# source_selector.net
KiCad netlist of a schematic drawn in EAGLE
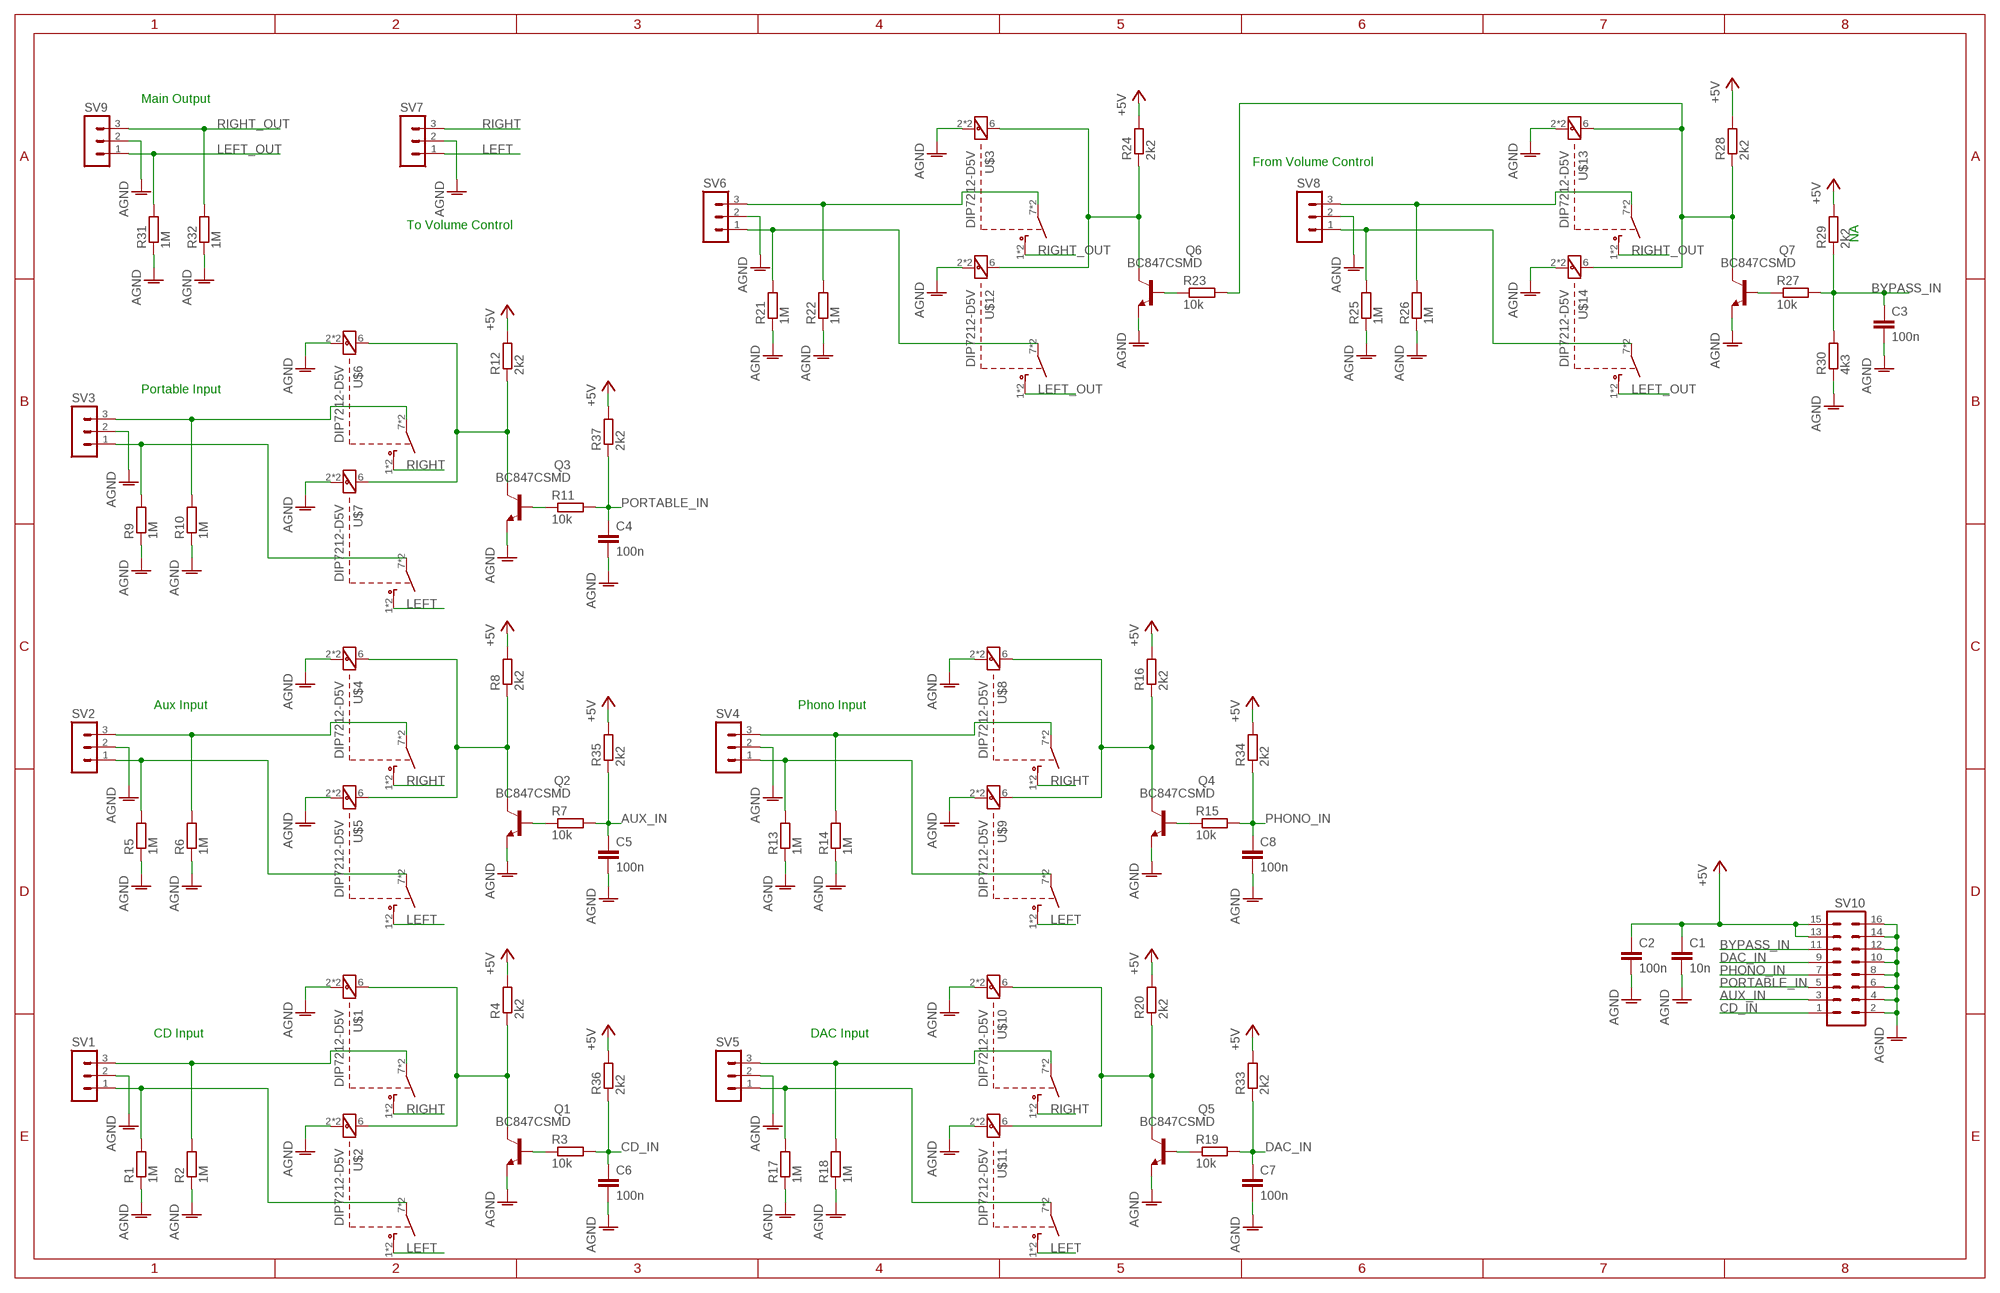
[diagram p0: schematic, sheet 1]

(export (version "E")
  (design (tool "Eeschema 10.0.6"))
  (components
    (comp (ref "C1")
      (value "10n")
      (footprint "eagle-import:C0603")
      (libsource (lib "eagle-import") (part "C-EUC0603"))
    )
    (comp (ref "C2")
      (value "100n")
      (footprint "eagle-import:C0603")
      (libsource (lib "eagle-import") (part "C-EUC0603"))
    )
    (comp (ref "C3")
      (value "100n")
      (footprint "eagle-import:C0603")
      (libsource (lib "eagle-import") (part "C-EUC0603"))
    )
    (comp (ref "C4")
      (value "100n")
      (footprint "eagle-import:C0603")
      (libsource (lib "eagle-import") (part "C-EUC0603"))
    )
    (comp (ref "C5")
      (value "100n")
      (footprint "eagle-import:C0603")
      (libsource (lib "eagle-import") (part "C-EUC0603"))
    )
    (comp (ref "C6")
      (value "100n")
      (footprint "eagle-import:C0603")
      (libsource (lib "eagle-import") (part "C-EUC0603"))
    )
    (comp (ref "C7")
      (value "100n")
      (footprint "eagle-import:C0603")
      (libsource (lib "eagle-import") (part "C-EUC0603"))
    )
    (comp (ref "C8")
      (value "100n")
      (footprint "eagle-import:C0603")
      (libsource (lib "eagle-import") (part "C-EUC0603"))
    )
    (comp (ref "Q1")
      (value "BC847CSMD")
      (footprint "eagle-import:SOT23")
      (libsource (lib "eagle-import") (part "BC847SMDC"))
    )
    (comp (ref "Q2")
      (value "BC847CSMD")
      (footprint "eagle-import:SOT23")
      (libsource (lib "eagle-import") (part "BC847SMDC"))
    )
    (comp (ref "Q3")
      (value "BC847CSMD")
      (footprint "eagle-import:SOT23")
      (libsource (lib "eagle-import") (part "BC847SMDC"))
    )
    (comp (ref "Q4")
      (value "BC847CSMD")
      (footprint "eagle-import:SOT23")
      (libsource (lib "eagle-import") (part "BC847SMDC"))
    )
    (comp (ref "Q5")
      (value "BC847CSMD")
      (footprint "eagle-import:SOT23")
      (libsource (lib "eagle-import") (part "BC847SMDC"))
    )
    (comp (ref "Q6")
      (value "BC847CSMD")
      (footprint "eagle-import:SOT23")
      (libsource (lib "eagle-import") (part "BC847SMDC"))
    )
    (comp (ref "Q7")
      (value "BC847CSMD")
      (footprint "eagle-import:SOT23")
      (libsource (lib "eagle-import") (part "BC847SMDC"))
    )
    (comp (ref "R1")
      (value "1M")
      (footprint "eagle-import:R0603")
      (libsource (lib "eagle-import") (part "R-EU_R0603"))
    )
    (comp (ref "R2")
      (value "1M")
      (footprint "eagle-import:R0603")
      (libsource (lib "eagle-import") (part "R-EU_R0603"))
    )
    (comp (ref "R3")
      (value "10k")
      (footprint "eagle-import:R0603")
      (libsource (lib "eagle-import") (part "R-EU_R0603"))
    )
    (comp (ref "R4")
      (value "2k2")
      (footprint "eagle-import:R0603")
      (libsource (lib "eagle-import") (part "R-EU_R0603"))
    )
    (comp (ref "R5")
      (value "1M")
      (footprint "eagle-import:R0603")
      (libsource (lib "eagle-import") (part "R-EU_R0603"))
    )
    (comp (ref "R6")
      (value "1M")
      (footprint "eagle-import:R0603")
      (libsource (lib "eagle-import") (part "R-EU_R0603"))
    )
    (comp (ref "R7")
      (value "10k")
      (footprint "eagle-import:R0603")
      (libsource (lib "eagle-import") (part "R-EU_R0603"))
    )
    (comp (ref "R8")
      (value "2k2")
      (footprint "eagle-import:R0603")
      (libsource (lib "eagle-import") (part "R-EU_R0603"))
    )
    (comp (ref "R9")
      (value "1M")
      (footprint "eagle-import:R0603")
      (libsource (lib "eagle-import") (part "R-EU_R0603"))
    )
    (comp (ref "R10")
      (value "1M")
      (footprint "eagle-import:R0603")
      (libsource (lib "eagle-import") (part "R-EU_R0603"))
    )
    (comp (ref "R11")
      (value "10k")
      (footprint "eagle-import:R0603")
      (libsource (lib "eagle-import") (part "R-EU_R0603"))
    )
    (comp (ref "R12")
      (value "2k2")
      (footprint "eagle-import:R0603")
      (libsource (lib "eagle-import") (part "R-EU_R0603"))
    )
    (comp (ref "R13")
      (value "1M")
      (footprint "eagle-import:R0603")
      (libsource (lib "eagle-import") (part "R-EU_R0603"))
    )
    (comp (ref "R14")
      (value "1M")
      (footprint "eagle-import:R0603")
      (libsource (lib "eagle-import") (part "R-EU_R0603"))
    )
    (comp (ref "R15")
      (value "10k")
      (footprint "eagle-import:R0603")
      (libsource (lib "eagle-import") (part "R-EU_R0603"))
    )
    (comp (ref "R16")
      (value "2k2")
      (footprint "eagle-import:R0603")
      (libsource (lib "eagle-import") (part "R-EU_R0603"))
    )
    (comp (ref "R17")
      (value "1M")
      (footprint "eagle-import:R0603")
      (libsource (lib "eagle-import") (part "R-EU_R0603"))
    )
    (comp (ref "R18")
      (value "1M")
      (footprint "eagle-import:R0603")
      (libsource (lib "eagle-import") (part "R-EU_R0603"))
    )
    (comp (ref "R19")
      (value "10k")
      (footprint "eagle-import:R0603")
      (libsource (lib "eagle-import") (part "R-EU_R0603"))
    )
    (comp (ref "R20")
      (value "2k2")
      (footprint "eagle-import:R0603")
      (libsource (lib "eagle-import") (part "R-EU_R0603"))
    )
    (comp (ref "R21")
      (value "1M")
      (footprint "eagle-import:R0603")
      (libsource (lib "eagle-import") (part "R-EU_R0603"))
    )
    (comp (ref "R22")
      (value "1M")
      (footprint "eagle-import:R0603")
      (libsource (lib "eagle-import") (part "R-EU_R0603"))
    )
    (comp (ref "R23")
      (value "10k")
      (footprint "eagle-import:R0603")
      (libsource (lib "eagle-import") (part "R-EU_R0603"))
    )
    (comp (ref "R24")
      (value "2k2")
      (footprint "eagle-import:R0603")
      (libsource (lib "eagle-import") (part "R-EU_R0603"))
    )
    (comp (ref "R25")
      (value "1M")
      (footprint "eagle-import:R0603")
      (libsource (lib "eagle-import") (part "R-EU_R0603"))
    )
    (comp (ref "R26")
      (value "1M")
      (footprint "eagle-import:R0603")
      (libsource (lib "eagle-import") (part "R-EU_R0603"))
    )
    (comp (ref "R27")
      (value "10k")
      (footprint "eagle-import:R0603")
      (libsource (lib "eagle-import") (part "R-EU_R0603"))
    )
    (comp (ref "R28")
      (value "2k2")
      (footprint "eagle-import:R0603")
      (libsource (lib "eagle-import") (part "R-EU_R0603"))
    )
    (comp (ref "R29")
      (value "2k2")
      (footprint "eagle-import:R0603")
      (libsource (lib "eagle-import") (part "R-EU_R0603"))
    )
    (comp (ref "R30")
      (value "4k3")
      (footprint "eagle-import:R0603")
      (libsource (lib "eagle-import") (part "R-EU_R0603"))
    )
    (comp (ref "R31")
      (value "1M")
      (footprint "eagle-import:R0603")
      (libsource (lib "eagle-import") (part "R-EU_R0603"))
    )
    (comp (ref "R32")
      (value "1M")
      (footprint "eagle-import:R0603")
      (libsource (lib "eagle-import") (part "R-EU_R0603"))
    )
    (comp (ref "R33")
      (value "2k2")
      (footprint "eagle-import:R0603")
      (libsource (lib "eagle-import") (part "R-EU_R0603"))
    )
    (comp (ref "R34")
      (value "2k2")
      (footprint "eagle-import:R0603")
      (libsource (lib "eagle-import") (part "R-EU_R0603"))
    )
    (comp (ref "R35")
      (value "2k2")
      (footprint "eagle-import:R0603")
      (libsource (lib "eagle-import") (part "R-EU_R0603"))
    )
    (comp (ref "R36")
      (value "2k2")
      (footprint "eagle-import:R0603")
      (libsource (lib "eagle-import") (part "R-EU_R0603"))
    )
    (comp (ref "R37")
      (value "2k2")
      (footprint "eagle-import:R0603")
      (libsource (lib "eagle-import") (part "R-EU_R0603"))
    )
    (comp (ref "SV1")
      (value "MA03-1")
      (footprint "eagle-import:MA03-1")
      (libsource (lib "eagle-import") (part "MA03-1"))
    )
    (comp (ref "SV2")
      (value "MA03-1")
      (footprint "eagle-import:MA03-1")
      (libsource (lib "eagle-import") (part "MA03-1"))
    )
    (comp (ref "SV3")
      (value "MA03-1")
      (footprint "eagle-import:MA03-1")
      (libsource (lib "eagle-import") (part "MA03-1"))
    )
    (comp (ref "SV4")
      (value "MA03-1")
      (footprint "eagle-import:MA03-1")
      (libsource (lib "eagle-import") (part "MA03-1"))
    )
    (comp (ref "SV5")
      (value "MA03-1")
      (footprint "eagle-import:MA03-1")
      (libsource (lib "eagle-import") (part "MA03-1"))
    )
    (comp (ref "SV6")
      (value "MA03-1")
      (footprint "eagle-import:MA03-1")
      (libsource (lib "eagle-import") (part "MA03-1"))
    )
    (comp (ref "SV7")
      (value "MA03-1")
      (footprint "eagle-import:MA03-1")
      (libsource (lib "eagle-import") (part "MA03-1"))
    )
    (comp (ref "SV8")
      (value "MA03-1")
      (footprint "eagle-import:MA03-1")
      (libsource (lib "eagle-import") (part "MA03-1"))
    )
    (comp (ref "SV9")
      (value "MA03-1")
      (footprint "eagle-import:MA03-1")
      (libsource (lib "eagle-import") (part "MA03-1"))
    )
    (comp (ref "SV10")
      (value "MA08-2")
      (footprint "eagle-import:MA08-2")
      (libsource (lib "eagle-import") (part "MA08-2"))
    )
    (comp (ref "U$1")
      (value "DIP7212-D5V")
      (footprint "eagle-import:DP-07")
      (libsource (lib "eagle-import") (part "DIP7212-D5V"))
    )
    (comp (ref "U$2")
      (value "DIP7212-D5V")
      (footprint "eagle-import:DP-07")
      (libsource (lib "eagle-import") (part "DIP7212-D5V"))
    )
    (comp (ref "U$3")
      (value "DIP7212-D5V")
      (footprint "eagle-import:DP-07")
      (libsource (lib "eagle-import") (part "DIP7212-D5V"))
    )
    (comp (ref "U$4")
      (value "DIP7212-D5V")
      (footprint "eagle-import:DP-07")
      (libsource (lib "eagle-import") (part "DIP7212-D5V"))
    )
    (comp (ref "U$5")
      (value "DIP7212-D5V")
      (footprint "eagle-import:DP-07")
      (libsource (lib "eagle-import") (part "DIP7212-D5V"))
    )
    (comp (ref "U$6")
      (value "DIP7212-D5V")
      (footprint "eagle-import:DP-07")
      (libsource (lib "eagle-import") (part "DIP7212-D5V"))
    )
    (comp (ref "U$7")
      (value "DIP7212-D5V")
      (footprint "eagle-import:DP-07")
      (libsource (lib "eagle-import") (part "DIP7212-D5V"))
    )
    (comp (ref "U$8")
      (value "DIP7212-D5V")
      (footprint "eagle-import:DP-07")
      (libsource (lib "eagle-import") (part "DIP7212-D5V"))
    )
    (comp (ref "U$9")
      (value "DIP7212-D5V")
      (footprint "eagle-import:DP-07")
      (libsource (lib "eagle-import") (part "DIP7212-D5V"))
    )
    (comp (ref "U$10")
      (value "DIP7212-D5V")
      (footprint "eagle-import:DP-07")
      (libsource (lib "eagle-import") (part "DIP7212-D5V"))
    )
    (comp (ref "U$11")
      (value "DIP7212-D5V")
      (footprint "eagle-import:DP-07")
      (libsource (lib "eagle-import") (part "DIP7212-D5V"))
    )
    (comp (ref "U$12")
      (value "DIP7212-D5V")
      (footprint "eagle-import:DP-07")
      (libsource (lib "eagle-import") (part "DIP7212-D5V"))
    )
    (comp (ref "U$13")
      (value "DIP7212-D5V")
      (footprint "eagle-import:DP-07")
      (libsource (lib "eagle-import") (part "DIP7212-D5V"))
    )
    (comp (ref "U$14")
      (value "DIP7212-D5V")
      (footprint "eagle-import:DP-07")
      (libsource (lib "eagle-import") (part "DIP7212-D5V"))
    )
  )
  (nets
    (net (code "1") (name "+5V") (class "Default")
      (node (ref "C1") (pin "1") (pinfunction "1_1") (pintype "passive"))
      (node (ref "C2") (pin "1") (pinfunction "1_1") (pintype "passive"))
      (node (ref "R12") (pin "2") (pinfunction "2_2") (pintype "passive"))
      (node (ref "R16") (pin "2") (pinfunction "2_2") (pintype "passive"))
      (node (ref "R20") (pin "2") (pinfunction "2_2") (pintype "passive"))
      (node (ref "R24") (pin "2") (pinfunction "2_2") (pintype "passive"))
      (node (ref "R28") (pin "2") (pinfunction "2_2") (pintype "passive"))
      (node (ref "R29") (pin "2") (pinfunction "2_2") (pintype "passive"))
      (node (ref "R33") (pin "2") (pinfunction "2_2") (pintype "passive"))
      (node (ref "R34") (pin "2") (pinfunction "2_2") (pintype "passive"))
      (node (ref "R35") (pin "2") (pinfunction "2_2") (pintype "passive"))
      (node (ref "R36") (pin "2") (pinfunction "2_2") (pintype "passive"))
      (node (ref "R37") (pin "2") (pinfunction "2_2") (pintype "passive"))
      (node (ref "R4") (pin "2") (pinfunction "2_2") (pintype "passive"))
      (node (ref "R8") (pin "2") (pinfunction "2_2") (pintype "passive"))
      (node (ref "SV10") (pin "13") (pinfunction "13_13") (pintype "passive"))
      (node (ref "SV10") (pin "15") (pinfunction "15_15") (pintype "passive"))
    )
    (net (code "2") (name "/AUX_IN") (class "Default")
      (node (ref "C5") (pin "1") (pinfunction "1_1") (pintype "passive"))
      (node (ref "R35") (pin "1") (pinfunction "1_1") (pintype "passive"))
      (node (ref "R7") (pin "2") (pinfunction "2_2") (pintype "passive"))
      (node (ref "SV10") (pin "3") (pinfunction "3_3") (pintype "passive"))
    )
    (net (code "3") (name "/BYPASS_IN") (class "Default")
      (node (ref "C3") (pin "1") (pinfunction "1_1") (pintype "passive"))
      (node (ref "R27") (pin "2") (pinfunction "2_2") (pintype "passive"))
      (node (ref "R29") (pin "1") (pinfunction "1_1") (pintype "passive"))
      (node (ref "R30") (pin "2") (pinfunction "2_2") (pintype "passive"))
      (node (ref "SV10") (pin "11") (pinfunction "11_11") (pintype "passive"))
    )
    (net (code "4") (name "/CD_IN") (class "Default")
      (node (ref "C6") (pin "1") (pinfunction "1_1") (pintype "passive"))
      (node (ref "R3") (pin "2") (pinfunction "2_2") (pintype "passive"))
      (node (ref "R36") (pin "1") (pinfunction "1_1") (pintype "passive"))
      (node (ref "SV10") (pin "1") (pinfunction "1_1") (pintype "passive"))
    )
    (net (code "5") (name "/DAC_IN") (class "Default")
      (node (ref "C7") (pin "1") (pinfunction "1_1") (pintype "passive"))
      (node (ref "R19") (pin "2") (pinfunction "2_2") (pintype "passive"))
      (node (ref "R33") (pin "1") (pinfunction "1_1") (pintype "passive"))
      (node (ref "SV10") (pin "9") (pinfunction "9_9") (pintype "passive"))
    )
    (net (code "6") (name "/LEFT") (class "Default")
      (node (ref "SV7") (pin "1") (pinfunction "1_1") (pintype "passive"))
      (node (ref "U$11") (pin "1") (pinfunction "6_1") (pintype "passive"))
      (node (ref "U$11") (pin "14") (pinfunction "6_14") (pintype "passive"))
      (node (ref "U$2") (pin "1") (pinfunction "6_1") (pintype "passive"))
      (node (ref "U$2") (pin "14") (pinfunction "6_14") (pintype "passive"))
      (node (ref "U$5") (pin "1") (pinfunction "6_1") (pintype "passive"))
      (node (ref "U$5") (pin "14") (pinfunction "6_14") (pintype "passive"))
      (node (ref "U$7") (pin "1") (pinfunction "6_1") (pintype "passive"))
      (node (ref "U$7") (pin "14") (pinfunction "6_14") (pintype "passive"))
      (node (ref "U$9") (pin "1") (pinfunction "6_1") (pintype "passive"))
      (node (ref "U$9") (pin "14") (pinfunction "6_14") (pintype "passive"))
    )
    (net (code "7") (name "/LEFT_OUT") (class "Default")
      (node (ref "R31") (pin "2") (pinfunction "2_2") (pintype "passive"))
      (node (ref "SV9") (pin "1") (pinfunction "1_1") (pintype "passive"))
      (node (ref "U$12") (pin "1") (pinfunction "6_1") (pintype "passive"))
      (node (ref "U$12") (pin "14") (pinfunction "6_14") (pintype "passive"))
      (node (ref "U$14") (pin "1") (pinfunction "6_1") (pintype "passive"))
      (node (ref "U$14") (pin "14") (pinfunction "6_14") (pintype "passive"))
    )
    (net (code "8") (name "/PHONO_IN") (class "Default")
      (node (ref "C8") (pin "1") (pinfunction "1_1") (pintype "passive"))
      (node (ref "R15") (pin "2") (pinfunction "2_2") (pintype "passive"))
      (node (ref "R34") (pin "1") (pinfunction "1_1") (pintype "passive"))
      (node (ref "SV10") (pin "7") (pinfunction "7_7") (pintype "passive"))
    )
    (net (code "9") (name "/PORTABLE_IN") (class "Default")
      (node (ref "C4") (pin "1") (pinfunction "1_1") (pintype "passive"))
      (node (ref "R11") (pin "2") (pinfunction "2_2") (pintype "passive"))
      (node (ref "R37") (pin "1") (pinfunction "1_1") (pintype "passive"))
      (node (ref "SV10") (pin "5") (pinfunction "5_5") (pintype "passive"))
    )
    (net (code "10") (name "/RIGHT") (class "Default")
      (node (ref "SV7") (pin "3") (pinfunction "3_3") (pintype "passive"))
      (node (ref "U$1") (pin "1") (pinfunction "6_1") (pintype "passive"))
      (node (ref "U$1") (pin "14") (pinfunction "6_14") (pintype "passive"))
      (node (ref "U$10") (pin "1") (pinfunction "6_1") (pintype "passive"))
      (node (ref "U$10") (pin "14") (pinfunction "6_14") (pintype "passive"))
      (node (ref "U$4") (pin "1") (pinfunction "6_1") (pintype "passive"))
      (node (ref "U$4") (pin "14") (pinfunction "6_14") (pintype "passive"))
      (node (ref "U$6") (pin "1") (pinfunction "6_1") (pintype "passive"))
      (node (ref "U$6") (pin "14") (pinfunction "6_14") (pintype "passive"))
      (node (ref "U$8") (pin "1") (pinfunction "6_1") (pintype "passive"))
      (node (ref "U$8") (pin "14") (pinfunction "6_14") (pintype "passive"))
    )
    (net (code "11") (name "/RIGHT_OUT") (class "Default")
      (node (ref "R32") (pin "2") (pinfunction "2_2") (pintype "passive"))
      (node (ref "SV9") (pin "3") (pinfunction "3_3") (pintype "passive"))
      (node (ref "U$13") (pin "1") (pinfunction "6_1") (pintype "passive"))
      (node (ref "U$13") (pin "14") (pinfunction "6_14") (pintype "passive"))
      (node (ref "U$3") (pin "1") (pinfunction "6_1") (pintype "passive"))
      (node (ref "U$3") (pin "14") (pinfunction "6_14") (pintype "passive"))
    )
    (net (code "12") (name "AGND") (class "Default")
      (node (ref "C1") (pin "2") (pinfunction "2_2") (pintype "passive"))
      (node (ref "C2") (pin "2") (pinfunction "2_2") (pintype "passive"))
      (node (ref "C3") (pin "2") (pinfunction "2_2") (pintype "passive"))
      (node (ref "C4") (pin "2") (pinfunction "2_2") (pintype "passive"))
      (node (ref "C5") (pin "2") (pinfunction "2_2") (pintype "passive"))
      (node (ref "C6") (pin "2") (pinfunction "2_2") (pintype "passive"))
      (node (ref "C7") (pin "2") (pinfunction "2_2") (pintype "passive"))
      (node (ref "C8") (pin "2") (pinfunction "2_2") (pintype "passive"))
      (node (ref "Q1") (pin "2") (pinfunction "E_2") (pintype "passive"))
      (node (ref "Q2") (pin "2") (pinfunction "E_2") (pintype "passive"))
      (node (ref "Q3") (pin "2") (pinfunction "E_2") (pintype "passive"))
      (node (ref "Q4") (pin "2") (pinfunction "E_2") (pintype "passive"))
      (node (ref "Q5") (pin "2") (pinfunction "E_2") (pintype "passive"))
      (node (ref "Q6") (pin "2") (pinfunction "E_2") (pintype "passive"))
      (node (ref "Q7") (pin "2") (pinfunction "E_2") (pintype "passive"))
      (node (ref "R1") (pin "1") (pinfunction "1_1") (pintype "passive"))
      (node (ref "R10") (pin "1") (pinfunction "1_1") (pintype "passive"))
      (node (ref "R13") (pin "1") (pinfunction "1_1") (pintype "passive"))
      (node (ref "R14") (pin "1") (pinfunction "1_1") (pintype "passive"))
      (node (ref "R17") (pin "1") (pinfunction "1_1") (pintype "passive"))
      (node (ref "R18") (pin "1") (pinfunction "1_1") (pintype "passive"))
      (node (ref "R2") (pin "1") (pinfunction "1_1") (pintype "passive"))
      (node (ref "R21") (pin "1") (pinfunction "1_1") (pintype "passive"))
      (node (ref "R22") (pin "1") (pinfunction "1_1") (pintype "passive"))
      (node (ref "R25") (pin "1") (pinfunction "1_1") (pintype "passive"))
      (node (ref "R26") (pin "1") (pinfunction "1_1") (pintype "passive"))
      (node (ref "R30") (pin "1") (pinfunction "1_1") (pintype "passive"))
      (node (ref "R31") (pin "1") (pinfunction "1_1") (pintype "passive"))
      (node (ref "R32") (pin "1") (pinfunction "1_1") (pintype "passive"))
      (node (ref "R5") (pin "1") (pinfunction "1_1") (pintype "passive"))
      (node (ref "R6") (pin "1") (pinfunction "1_1") (pintype "passive"))
      (node (ref "R9") (pin "1") (pinfunction "1_1") (pintype "passive"))
      (node (ref "SV1") (pin "2") (pinfunction "2_2") (pintype "passive"))
      (node (ref "SV10") (pin "10") (pinfunction "10_10") (pintype "passive"))
      (node (ref "SV10") (pin "12") (pinfunction "12_12") (pintype "passive"))
      (node (ref "SV10") (pin "14") (pinfunction "14_14") (pintype "passive"))
      (node (ref "SV10") (pin "16") (pinfunction "16_16") (pintype "passive"))
      (node (ref "SV10") (pin "2") (pinfunction "2_2") (pintype "passive"))
      (node (ref "SV10") (pin "4") (pinfunction "4_4") (pintype "passive"))
      (node (ref "SV10") (pin "6") (pinfunction "6_6") (pintype "passive"))
      (node (ref "SV10") (pin "8") (pinfunction "8_8") (pintype "passive"))
      (node (ref "SV2") (pin "2") (pinfunction "2_2") (pintype "passive"))
      (node (ref "SV3") (pin "2") (pinfunction "2_2") (pintype "passive"))
      (node (ref "SV4") (pin "2") (pinfunction "2_2") (pintype "passive"))
      (node (ref "SV5") (pin "2") (pinfunction "2_2") (pintype "passive"))
      (node (ref "SV6") (pin "2") (pinfunction "2_2") (pintype "passive"))
      (node (ref "SV7") (pin "2") (pinfunction "2_2") (pintype "passive"))
      (node (ref "SV8") (pin "2") (pinfunction "2_2") (pintype "passive"))
      (node (ref "SV9") (pin "2") (pinfunction "2_2") (pintype "passive"))
      (node (ref "U$1") (pin "13") (pinfunction "1_13") (pintype "passive"))
      (node (ref "U$1") (pin "2") (pinfunction "1_2") (pintype "passive"))
      (node (ref "U$10") (pin "13") (pinfunction "1_13") (pintype "passive"))
      (node (ref "U$10") (pin "2") (pinfunction "1_2") (pintype "passive"))
      (node (ref "U$11") (pin "13") (pinfunction "1_13") (pintype "passive"))
      (node (ref "U$11") (pin "2") (pinfunction "1_2") (pintype "passive"))
      (node (ref "U$12") (pin "13") (pinfunction "1_13") (pintype "passive"))
      (node (ref "U$12") (pin "2") (pinfunction "1_2") (pintype "passive"))
      (node (ref "U$13") (pin "13") (pinfunction "1_13") (pintype "passive"))
      (node (ref "U$13") (pin "2") (pinfunction "1_2") (pintype "passive"))
      (node (ref "U$14") (pin "13") (pinfunction "1_13") (pintype "passive"))
      (node (ref "U$14") (pin "2") (pinfunction "1_2") (pintype "passive"))
      (node (ref "U$2") (pin "13") (pinfunction "1_13") (pintype "passive"))
      (node (ref "U$2") (pin "2") (pinfunction "1_2") (pintype "passive"))
      (node (ref "U$3") (pin "13") (pinfunction "1_13") (pintype "passive"))
      (node (ref "U$3") (pin "2") (pinfunction "1_2") (pintype "passive"))
      (node (ref "U$4") (pin "13") (pinfunction "1_13") (pintype "passive"))
      (node (ref "U$4") (pin "2") (pinfunction "1_2") (pintype "passive"))
      (node (ref "U$5") (pin "13") (pinfunction "1_13") (pintype "passive"))
      (node (ref "U$5") (pin "2") (pinfunction "1_2") (pintype "passive"))
      (node (ref "U$6") (pin "13") (pinfunction "1_13") (pintype "passive"))
      (node (ref "U$6") (pin "2") (pinfunction "1_2") (pintype "passive"))
      (node (ref "U$7") (pin "13") (pinfunction "1_13") (pintype "passive"))
      (node (ref "U$7") (pin "2") (pinfunction "1_2") (pintype "passive"))
      (node (ref "U$8") (pin "13") (pinfunction "1_13") (pintype "passive"))
      (node (ref "U$8") (pin "2") (pinfunction "1_2") (pintype "passive"))
      (node (ref "U$9") (pin "13") (pinfunction "1_13") (pintype "passive"))
      (node (ref "U$9") (pin "2") (pinfunction "1_2") (pintype "passive"))
    )
    (net (code "13") (name "Net-(Q1-B)") (class "Default")
      (node (ref "Q1") (pin "1") (pinfunction "B_1") (pintype "passive"))
      (node (ref "R3") (pin "1") (pinfunction "1_1") (pintype "passive"))
    )
    (net (code "14") (name "Net-(Q1-C)") (class "Default")
      (node (ref "Q1") (pin "3") (pinfunction "C_3") (pintype "passive"))
      (node (ref "R4") (pin "1") (pinfunction "1_1") (pintype "passive"))
      (node (ref "U$1") (pin "6") (pinfunction "2_6") (pintype "passive"))
      (node (ref "U$2") (pin "6") (pinfunction "2_6") (pintype "passive"))
    )
    (net (code "15") (name "Net-(Q2-B)") (class "Default")
      (node (ref "Q2") (pin "1") (pinfunction "B_1") (pintype "passive"))
      (node (ref "R7") (pin "1") (pinfunction "1_1") (pintype "passive"))
    )
    (net (code "16") (name "Net-(Q2-C)") (class "Default")
      (node (ref "Q2") (pin "3") (pinfunction "C_3") (pintype "passive"))
      (node (ref "R8") (pin "1") (pinfunction "1_1") (pintype "passive"))
      (node (ref "U$4") (pin "6") (pinfunction "2_6") (pintype "passive"))
      (node (ref "U$5") (pin "6") (pinfunction "2_6") (pintype "passive"))
    )
    (net (code "17") (name "Net-(Q3-B)") (class "Default")
      (node (ref "Q3") (pin "1") (pinfunction "B_1") (pintype "passive"))
      (node (ref "R11") (pin "1") (pinfunction "1_1") (pintype "passive"))
    )
    (net (code "18") (name "Net-(Q3-C)") (class "Default")
      (node (ref "Q3") (pin "3") (pinfunction "C_3") (pintype "passive"))
      (node (ref "R12") (pin "1") (pinfunction "1_1") (pintype "passive"))
      (node (ref "U$6") (pin "6") (pinfunction "2_6") (pintype "passive"))
      (node (ref "U$7") (pin "6") (pinfunction "2_6") (pintype "passive"))
    )
    (net (code "19") (name "Net-(Q4-B)") (class "Default")
      (node (ref "Q4") (pin "1") (pinfunction "B_1") (pintype "passive"))
      (node (ref "R15") (pin "1") (pinfunction "1_1") (pintype "passive"))
    )
    (net (code "20") (name "Net-(Q4-C)") (class "Default")
      (node (ref "Q4") (pin "3") (pinfunction "C_3") (pintype "passive"))
      (node (ref "R16") (pin "1") (pinfunction "1_1") (pintype "passive"))
      (node (ref "U$8") (pin "6") (pinfunction "2_6") (pintype "passive"))
      (node (ref "U$9") (pin "6") (pinfunction "2_6") (pintype "passive"))
    )
    (net (code "21") (name "Net-(Q5-B)") (class "Default")
      (node (ref "Q5") (pin "1") (pinfunction "B_1") (pintype "passive"))
      (node (ref "R19") (pin "1") (pinfunction "1_1") (pintype "passive"))
    )
    (net (code "22") (name "Net-(Q5-C)") (class "Default")
      (node (ref "Q5") (pin "3") (pinfunction "C_3") (pintype "passive"))
      (node (ref "R20") (pin "1") (pinfunction "1_1") (pintype "passive"))
      (node (ref "U$10") (pin "6") (pinfunction "2_6") (pintype "passive"))
      (node (ref "U$11") (pin "6") (pinfunction "2_6") (pintype "passive"))
    )
    (net (code "23") (name "Net-(Q6-B)") (class "Default")
      (node (ref "Q6") (pin "1") (pinfunction "B_1") (pintype "passive"))
      (node (ref "R23") (pin "1") (pinfunction "1_1") (pintype "passive"))
    )
    (net (code "24") (name "Net-(Q6-C)") (class "Default")
      (node (ref "Q6") (pin "3") (pinfunction "C_3") (pintype "passive"))
      (node (ref "R24") (pin "1") (pinfunction "1_1") (pintype "passive"))
      (node (ref "U$12") (pin "6") (pinfunction "2_6") (pintype "passive"))
      (node (ref "U$3") (pin "6") (pinfunction "2_6") (pintype "passive"))
    )
    (net (code "25") (name "Net-(Q7-B)") (class "Default")
      (node (ref "Q7") (pin "1") (pinfunction "B_1") (pintype "passive"))
      (node (ref "R27") (pin "1") (pinfunction "1_1") (pintype "passive"))
    )
    (net (code "26") (name "Net-(Q7-C)") (class "Default")
      (node (ref "Q7") (pin "3") (pinfunction "C_3") (pintype "passive"))
      (node (ref "R23") (pin "2") (pinfunction "2_2") (pintype "passive"))
      (node (ref "R28") (pin "1") (pinfunction "1_1") (pintype "passive"))
      (node (ref "U$13") (pin "6") (pinfunction "2_6") (pintype "passive"))
      (node (ref "U$14") (pin "6") (pinfunction "2_6") (pintype "passive"))
    )
    (net (code "27") (name "Net-(R1-Pad2)") (class "Default")
      (node (ref "R1") (pin "2") (pinfunction "2_2") (pintype "passive"))
      (node (ref "SV1") (pin "1") (pinfunction "1_1") (pintype "passive"))
      (node (ref "U$2") (pin "7") (pinfunction "5_7") (pintype "passive"))
      (node (ref "U$2") (pin "8") (pinfunction "5_8") (pintype "passive"))
    )
    (net (code "28") (name "Net-(R2-Pad2)") (class "Default")
      (node (ref "R2") (pin "2") (pinfunction "2_2") (pintype "passive"))
      (node (ref "SV1") (pin "3") (pinfunction "3_3") (pintype "passive"))
      (node (ref "U$1") (pin "7") (pinfunction "5_7") (pintype "passive"))
      (node (ref "U$1") (pin "8") (pinfunction "5_8") (pintype "passive"))
    )
    (net (code "29") (name "Net-(R5-Pad2)") (class "Default")
      (node (ref "R5") (pin "2") (pinfunction "2_2") (pintype "passive"))
      (node (ref "SV2") (pin "1") (pinfunction "1_1") (pintype "passive"))
      (node (ref "U$5") (pin "7") (pinfunction "5_7") (pintype "passive"))
      (node (ref "U$5") (pin "8") (pinfunction "5_8") (pintype "passive"))
    )
    (net (code "30") (name "Net-(R6-Pad2)") (class "Default")
      (node (ref "R6") (pin "2") (pinfunction "2_2") (pintype "passive"))
      (node (ref "SV2") (pin "3") (pinfunction "3_3") (pintype "passive"))
      (node (ref "U$4") (pin "7") (pinfunction "5_7") (pintype "passive"))
      (node (ref "U$4") (pin "8") (pinfunction "5_8") (pintype "passive"))
    )
    (net (code "31") (name "Net-(R9-Pad2)") (class "Default")
      (node (ref "R9") (pin "2") (pinfunction "2_2") (pintype "passive"))
      (node (ref "SV3") (pin "1") (pinfunction "1_1") (pintype "passive"))
      (node (ref "U$7") (pin "7") (pinfunction "5_7") (pintype "passive"))
      (node (ref "U$7") (pin "8") (pinfunction "5_8") (pintype "passive"))
    )
    (net (code "32") (name "Net-(R10-Pad2)") (class "Default")
      (node (ref "R10") (pin "2") (pinfunction "2_2") (pintype "passive"))
      (node (ref "SV3") (pin "3") (pinfunction "3_3") (pintype "passive"))
      (node (ref "U$6") (pin "7") (pinfunction "5_7") (pintype "passive"))
      (node (ref "U$6") (pin "8") (pinfunction "5_8") (pintype "passive"))
    )
    (net (code "33") (name "Net-(R13-Pad2)") (class "Default")
      (node (ref "R13") (pin "2") (pinfunction "2_2") (pintype "passive"))
      (node (ref "SV4") (pin "1") (pinfunction "1_1") (pintype "passive"))
      (node (ref "U$9") (pin "7") (pinfunction "5_7") (pintype "passive"))
      (node (ref "U$9") (pin "8") (pinfunction "5_8") (pintype "passive"))
    )
    (net (code "34") (name "Net-(R14-Pad2)") (class "Default")
      (node (ref "R14") (pin "2") (pinfunction "2_2") (pintype "passive"))
      (node (ref "SV4") (pin "3") (pinfunction "3_3") (pintype "passive"))
      (node (ref "U$8") (pin "7") (pinfunction "5_7") (pintype "passive"))
      (node (ref "U$8") (pin "8") (pinfunction "5_8") (pintype "passive"))
    )
    (net (code "35") (name "Net-(R17-Pad2)") (class "Default")
      (node (ref "R17") (pin "2") (pinfunction "2_2") (pintype "passive"))
      (node (ref "SV5") (pin "1") (pinfunction "1_1") (pintype "passive"))
      (node (ref "U$11") (pin "7") (pinfunction "5_7") (pintype "passive"))
      (node (ref "U$11") (pin "8") (pinfunction "5_8") (pintype "passive"))
    )
    (net (code "36") (name "Net-(R18-Pad2)") (class "Default")
      (node (ref "R18") (pin "2") (pinfunction "2_2") (pintype "passive"))
      (node (ref "SV5") (pin "3") (pinfunction "3_3") (pintype "passive"))
      (node (ref "U$10") (pin "7") (pinfunction "5_7") (pintype "passive"))
      (node (ref "U$10") (pin "8") (pinfunction "5_8") (pintype "passive"))
    )
    (net (code "37") (name "Net-(R21-Pad2)") (class "Default")
      (node (ref "R21") (pin "2") (pinfunction "2_2") (pintype "passive"))
      (node (ref "SV6") (pin "1") (pinfunction "1_1") (pintype "passive"))
      (node (ref "U$12") (pin "7") (pinfunction "5_7") (pintype "passive"))
      (node (ref "U$12") (pin "8") (pinfunction "5_8") (pintype "passive"))
    )
    (net (code "38") (name "Net-(R22-Pad2)") (class "Default")
      (node (ref "R22") (pin "2") (pinfunction "2_2") (pintype "passive"))
      (node (ref "SV6") (pin "3") (pinfunction "3_3") (pintype "passive"))
      (node (ref "U$3") (pin "7") (pinfunction "5_7") (pintype "passive"))
      (node (ref "U$3") (pin "8") (pinfunction "5_8") (pintype "passive"))
    )
    (net (code "39") (name "Net-(R25-Pad2)") (class "Default")
      (node (ref "R25") (pin "2") (pinfunction "2_2") (pintype "passive"))
      (node (ref "SV8") (pin "1") (pinfunction "1_1") (pintype "passive"))
      (node (ref "U$14") (pin "7") (pinfunction "5_7") (pintype "passive"))
      (node (ref "U$14") (pin "8") (pinfunction "5_8") (pintype "passive"))
    )
    (net (code "40") (name "Net-(R26-Pad2)") (class "Default")
      (node (ref "R26") (pin "2") (pinfunction "2_2") (pintype "passive"))
      (node (ref "SV8") (pin "3") (pinfunction "3_3") (pintype "passive"))
      (node (ref "U$13") (pin "7") (pinfunction "5_7") (pintype "passive"))
      (node (ref "U$13") (pin "8") (pinfunction "5_8") (pintype "passive"))
    )
  )
)
